# 02_Project.net
KiCad netlist of a schematic drawn in Altium Designer
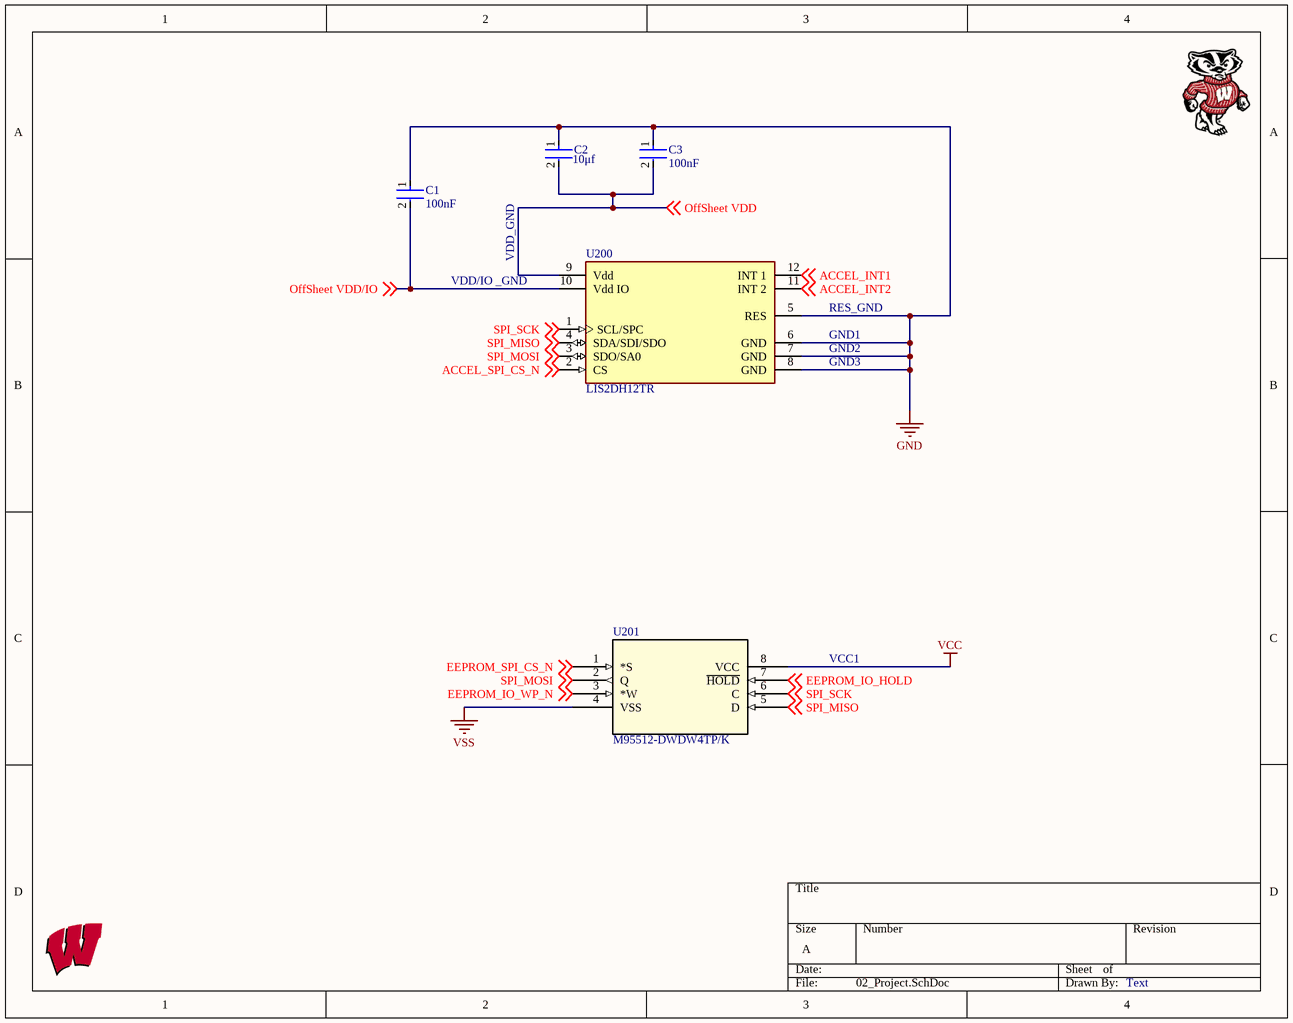
[diagram p0: 02_Project.SchDoc]

(export (version "E")
  (design (tool "Eeschema 10.0.6"))
  (components
    (comp (ref "C1")
      (value "100nF")
      (footprint "FP-C0805C-DN-MFG")
      (description "CAP CER 0.1UF 50V X7R 0805")
      (fields
        (field (name "MANUFACTURER PART NUMBER") "C0805C104K5RACTU")
        (field (name "MANUFACTURER") "KEMET")
      )
      (libsource (lib "Altium Content Vault") (part "b4654b650e69147ec39a6b967a45e02"))
    )
    (comp (ref "C2")
      (value "10μf")
      (footprint "FP-GRM21B-0_15-IPC_C")
      (description "Chip Multilayer Ceramic Capacitors for General Purpose, 0805, 10uF, X5R, 15%, 10%, 25V")
      (fields (field (name "VOLTAGE") "25V") (field (name "TOLERANCE") "10%"))
      (libsource (lib "Altium Content Vault") (part "b4654b650e69147ec39a6b967a45e02"))
    )
    (comp (ref "C3")
      (value "100nF")
      (footprint "FP-C0805C-DN-MFG")
      (description "CAP CER 0.1UF 50V X7R 0805")
      (fields
        (field (name "MANUFACTURER PART NUMBER") "C0805C104K5RACTU")
        (field (name "MANUFACTURER") "KEMET")
      )
      (libsource (lib "Altium Content Vault") (part "b4654b650e69147ec39a6b967a45e02"))
    )
    (comp (ref "U200")
      (value "LIS2DH12TR")
      (footprint "FP-LGA-12-8365767-MFG")
      (description "ACCEL 2-16G I2C/SPI 12LGA")
      (libsource (lib "Altium Content Vault") (part "43ad9b989a05401887db1079274fe63"))
    )
    (comp (ref "U201")
      (value "M95512-DWDW4TP/K")
      (footprint "TSSOP8_169MILS_DW_STM-M")
      (description "EEPROM Serial-SPI 512K-bit 64K x 8 3.3V/5V Automotive 8-Pin TSSOP T/R")
      (fields (field (name "COPYRIGHT") "Copyright (C) 2022 Ultra Librarian. All rights reserved."))
      (libsource (lib "ece353-2022") (part "M95512-DWDW4TP/K"))
    )
  )
  (nets
    (net (code "1") (name "ACCEL_INT1") (class "Default")
      (node (ref "U200") (pin "12") (pinfunction "INT_1_12") (pintype "passive"))
    )
    (net (code "2") (name "ACCEL_INT2") (class "Default")
      (node (ref "U200") (pin "11") (pinfunction "INT_2_11") (pintype "passive"))
    )
    (net (code "3") (name "ACCEL_SPI_CS_N") (class "Default")
      (node (ref "U200") (pin "2") (pinfunction "CS_2") (pintype "input"))
    )
    (net (code "4") (name "EEPROM_IO_HOLD") (class "Default")
      (node (ref "U201") (pin "7") (pinfunction "~{HOLD}_7") (pintype "input"))
    )
    (net (code "5") (name "EEPROM_IO_WP_N") (class "Default")
      (node (ref "U201") (pin "3") (pinfunction "*W_3") (pintype "input"))
    )
    (net (code "6") (name "EEPROM_SPI_CS_N") (class "Default")
      (node (ref "U201") (pin "1") (pinfunction "*S_1") (pintype "input"))
    )
    (net (code "7") (name "GND") (class "Default")
      (node (ref "C1") (pin "1") (pinfunction "1_1") (pintype "passive"))
      (node (ref "C2") (pin "1") (pinfunction "1_1") (pintype "passive"))
      (node (ref "C3") (pin "1") (pinfunction "1_1") (pintype "passive"))
      (node (ref "U200") (pin "5") (pinfunction "RES_5") (pintype "power_in"))
      (node (ref "U200") (pin "6") (pinfunction "GND_6") (pintype "power_in"))
      (node (ref "U200") (pin "7") (pinfunction "GND_7") (pintype "power_in"))
      (node (ref "U200") (pin "8") (pinfunction "GND_8") (pintype "power_in"))
    )
    (net (code "8") (name "OffSheet VDD") (class "Default")
      (node (ref "C2") (pin "2") (pinfunction "2_2") (pintype "passive"))
      (node (ref "C3") (pin "2") (pinfunction "2_2") (pintype "passive"))
      (node (ref "U200") (pin "9") (pinfunction "Vdd_9") (pintype "power_in"))
    )
    (net (code "9") (name "OffSheet VDD{slash}IO") (class "Default")
      (node (ref "C1") (pin "2") (pinfunction "2_2") (pintype "passive"))
      (node (ref "U200") (pin "10") (pinfunction "Vdd_IO_10") (pintype "power_in"))
    )
    (net (code "10") (name "SPI_MISO") (class "Default")
      (node (ref "U200") (pin "4") (pinfunction "SDA/SDI/SDO_4") (pintype "bidirectional"))
      (node (ref "U201") (pin "5") (pinfunction "D_5") (pintype "input"))
    )
    (net (code "11") (name "SPI_MOSI") (class "Default")
      (node (ref "U200") (pin "3") (pinfunction "SDO/SA0_3") (pintype "bidirectional"))
      (node (ref "U201") (pin "2") (pinfunction "Q_2") (pintype "output"))
    )
    (net (code "12") (name "SPI_SCK") (class "Default")
      (node (ref "U200") (pin "1") (pinfunction "SCL/SPC_1") (pintype "input"))
      (node (ref "U201") (pin "6") (pinfunction "C_6") (pintype "input"))
    )
    (net (code "13") (name "VCC") (class "Default")
      (node (ref "U201") (pin "8") (pinfunction "VCC_8") (pintype "power_in"))
    )
    (net (code "14") (name "VSS") (class "Default")
      (node (ref "U201") (pin "4") (pinfunction "VSS_4") (pintype "passive"))
    )
  )
)
